# Heaters.net
KiCad netlist of a schematic drawn in Altium Designer
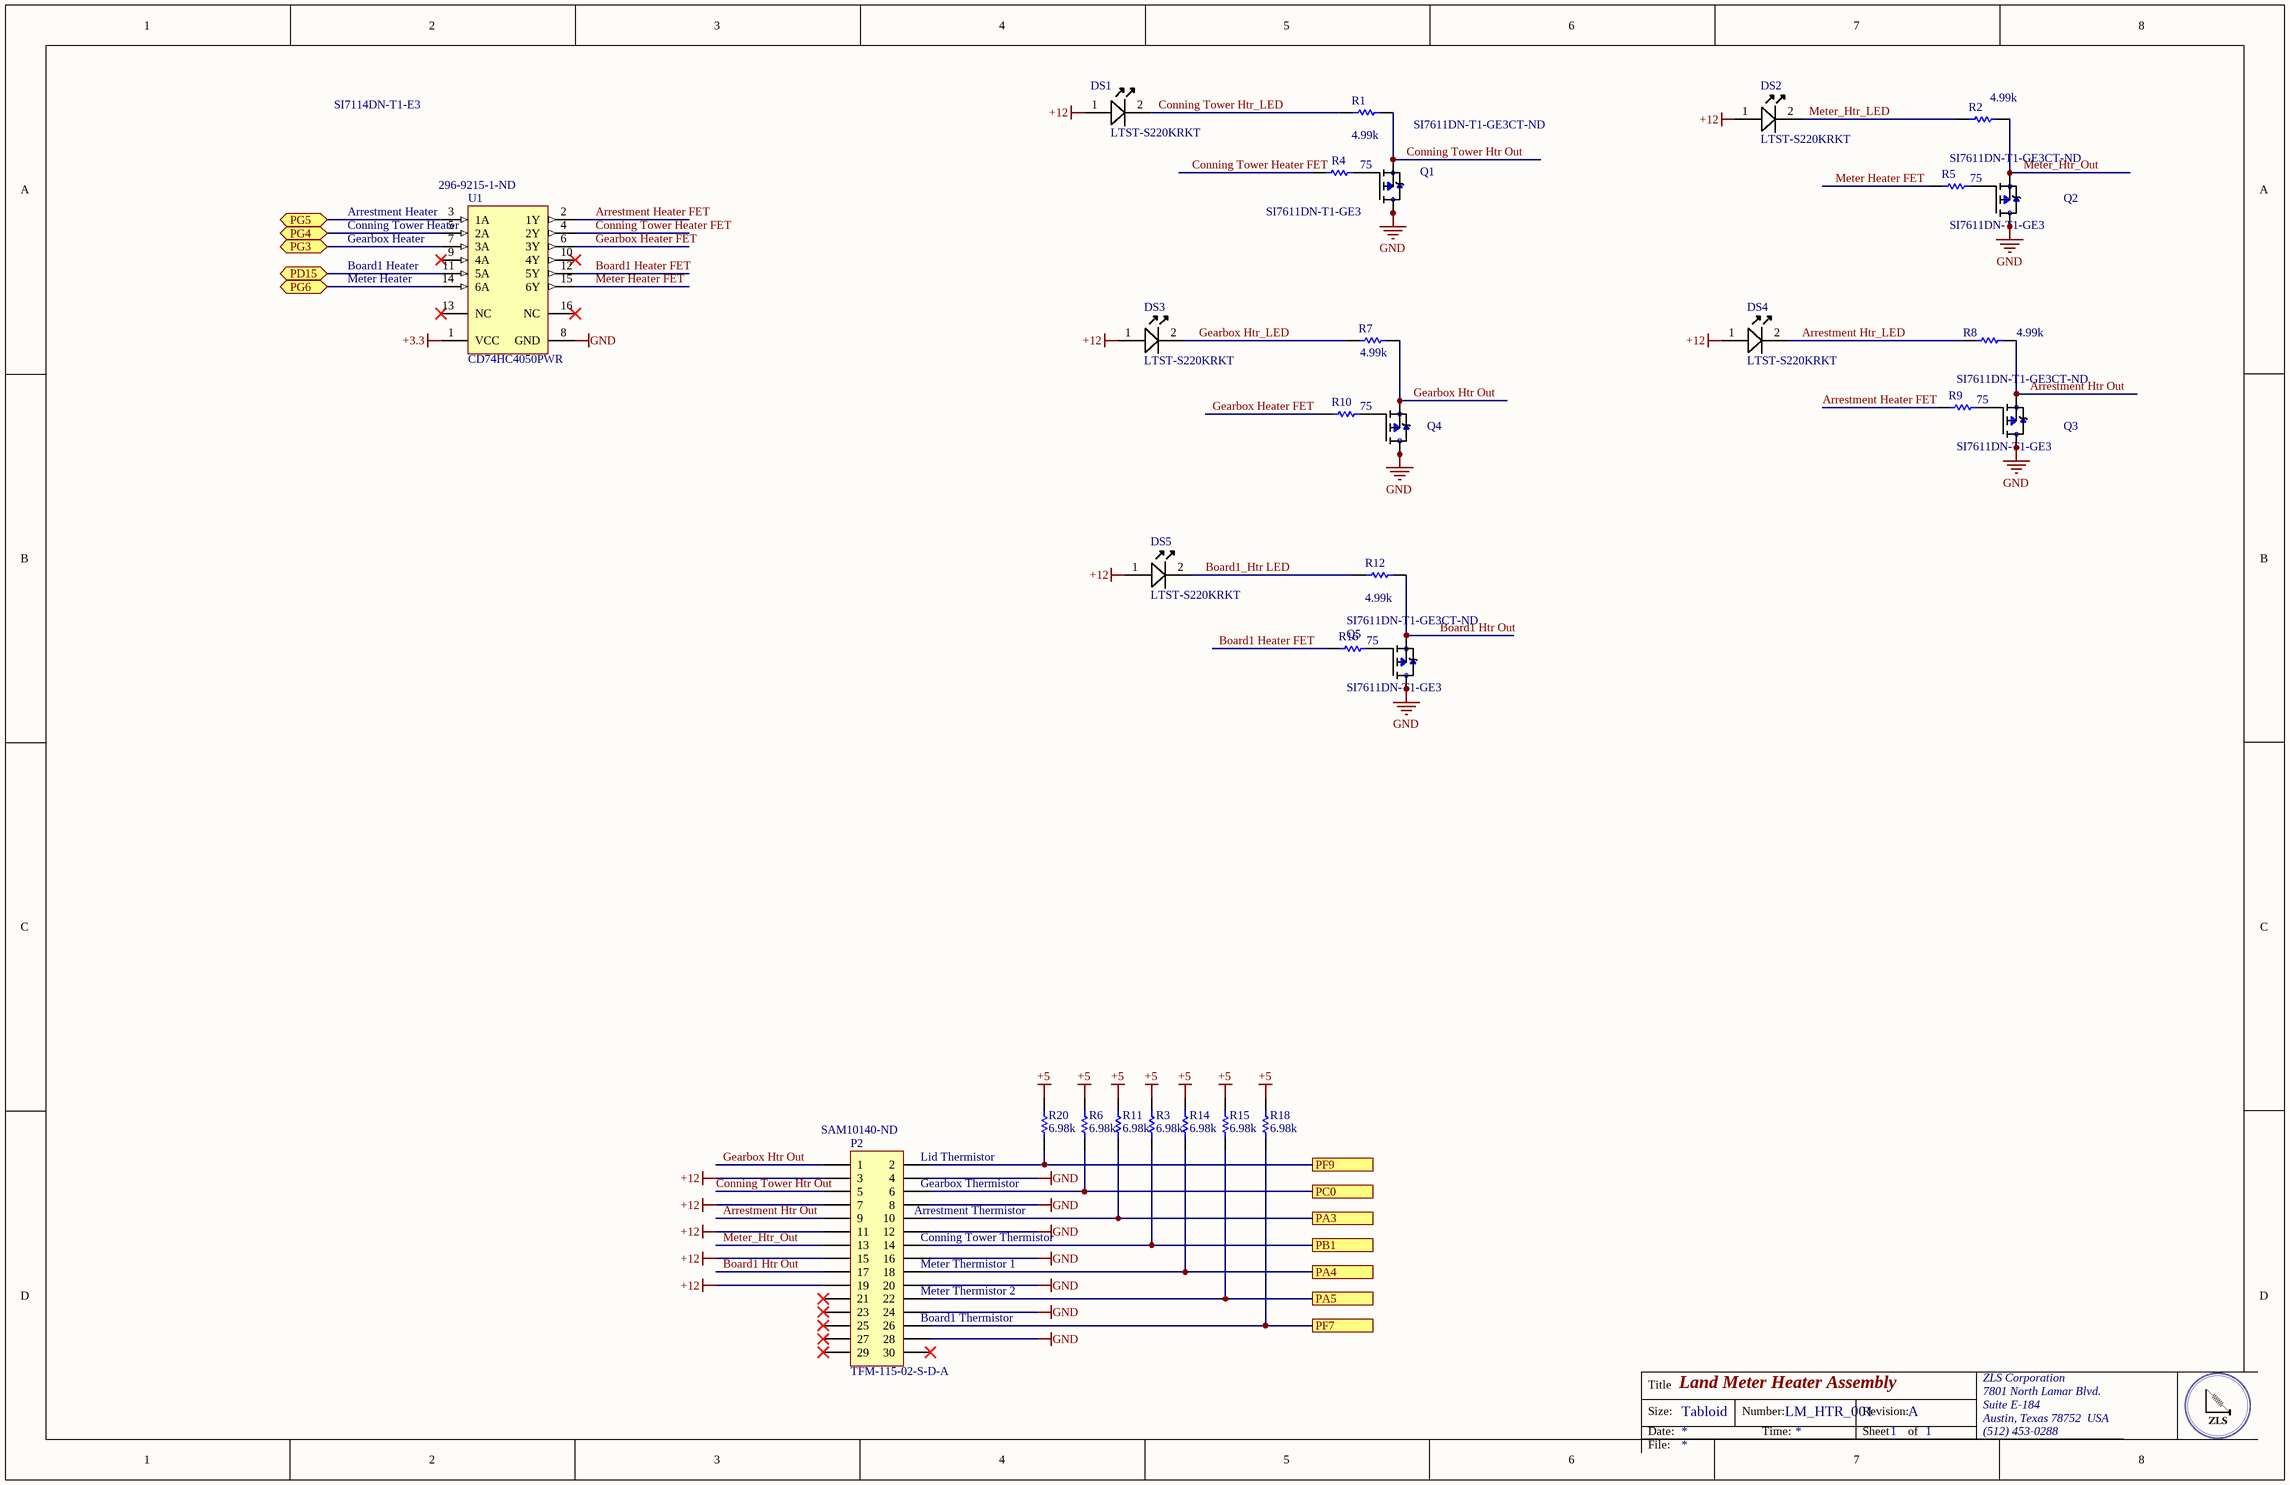
[diagram p0: Heaters.SchDoc]

(export (version "E")
  (design (tool "Eeschema 10.0.6"))
  (components
    (comp (ref "DS1")
      (value "Visible Name Value Type    False Description Lite-On LTST-S220KRKT Red LED, 631 nm 2012 (0805) Side View, Rectangle Lens SMD package STRING")
      (footprint "0805C_L")
      (fields
        (field (name "MANUFACTURER") "Vishay / Lite-On")
        (field (name "MANUFACTURER PART NUMBER") "LTST-S220KRKT")
      )
      (libsource (lib "*") (part "LED A/K"))
    )
    (comp (ref "DS2")
      (value "Visible Name Value Type    False Description Lite-On LTST-S220KRKT Red LED, 631 nm 2012 (0805) Side View, Rectangle Lens SMD package STRING")
      (footprint "0805C_L")
      (fields
        (field (name "MANUFACTURER") "Vishay / Lite-On")
        (field (name "MANUFACTURER PART NUMBER") "LTST-S220KRKT")
      )
      (libsource (lib "*") (part "LED A/K"))
    )
    (comp (ref "DS3")
      (value "Visible Name Value Type    False Description Lite-On LTST-S220KRKT Red LED, 631 nm 2012 (0805) Side View, Rectangle Lens SMD package STRING")
      (footprint "0805C_L")
      (fields
        (field (name "MANUFACTURER") "Vishay / Lite-On")
        (field (name "MANUFACTURER PART NUMBER") "LTST-S220KRKT")
      )
      (libsource (lib "*") (part "LED A/K"))
    )
    (comp (ref "DS4")
      (value "Visible Name Value Type    False Description Lite-On LTST-S220KRKT Red LED, 631 nm 2012 (0805) Side View, Rectangle Lens SMD package STRING")
      (footprint "0805C_L")
      (fields
        (field (name "MANUFACTURER") "Vishay / Lite-On")
        (field (name "MANUFACTURER PART NUMBER") "LTST-S220KRKT")
      )
      (libsource (lib "*") (part "LED A/K"))
    )
    (comp (ref "DS5")
      (value "Visible Name Value Type    False Description Lite-On LTST-S220KRKT Red LED, 631 nm 2012 (0805) Side View, Rectangle Lens SMD package STRING")
      (footprint "0805C_L")
      (fields
        (field (name "MANUFACTURER") "Vishay / Lite-On")
        (field (name "MANUFACTURER PART NUMBER") "LTST-S220KRKT")
      )
      (libsource (lib "*") (part "LED A/K"))
    )
    (comp (ref "P2")
      (value "TFM-115-02-S-D-A")
      (footprint "TFM-115-02-S-D-A - duplicate")
      (description "Header, 15-Pin, Dual row, Right Angle")
      (fields
        (field (name "SUPPLIER PART NUMBER 1") "SAM10140-ND")
        (field (name "MANUFACTURER") "Samtec")
        (field (name "PUBLISHER") "Altium Limited")
      )
      (libsource (lib "Miscellaneous Connectors") (part "Header 15X2H"))
    )
    (comp (ref "Q1")
      (value "SI7611DN-T1-GE3")
      (footprint "*VISHAY_SIS468DN-T1-GE3")
      (description "P-Channel 40 V 0.025 Ohm 39 W Surface Mount Power Mosfet - PowerPAK-1212-8")
      (fields
        (field (name "DIGI-KEY_PART_NUMBER") "SI7611DN-T1-GE3CT-ND")
        (field (name "MF") "Vishay Siliconix")
        (field (name "SUPPLIER PART NUMBER 1") "SI7611DN-T1-GE3CT-ND")
      )
      (libsource (lib "SI7611DN-T1-GE3") (part "SI7611DN-T1-GE3"))
    )
    (comp (ref "Q2")
      (value "SI7611DN-T1-GE3")
      (footprint "*VISHAY_SIS468DN-T1-GE3")
      (description "P-Channel 40 V 0.025 Ohm 39 W Surface Mount Power Mosfet - PowerPAK-1212-8")
      (fields
        (field (name "DIGI-KEY_PART_NUMBER") "SI7611DN-T1-GE3CT-ND")
        (field (name "MF") "Vishay Siliconix")
        (field (name "SUPPLIER PART NUMBER 1") "SI7611DN-T1-GE3CT-ND")
      )
      (libsource (lib "SI7611DN-T1-GE3") (part "SI7611DN-T1-GE3"))
    )
    (comp (ref "Q3")
      (value "SI7611DN-T1-GE3")
      (footprint "*VISHAY_SIS468DN-T1-GE3")
      (description "P-Channel 40 V 0.025 Ohm 39 W Surface Mount Power Mosfet - PowerPAK-1212-8")
      (fields
        (field (name "DIGI-KEY_PART_NUMBER") "SI7611DN-T1-GE3CT-ND")
        (field (name "MF") "Vishay Siliconix")
        (field (name "SUPPLIER PART NUMBER 1") "SI7611DN-T1-GE3CT-ND")
      )
      (libsource (lib "SI7611DN-T1-GE3") (part "SI7611DN-T1-GE3"))
    )
    (comp (ref "Q4")
      (value "SI7611DN-T1-GE3")
      (footprint "*VISHAY_SIS468DN-T1-GE3")
      (description "P-Channel 40 V 0.025 Ohm 39 W Surface Mount Power Mosfet - PowerPAK-1212-8")
      (fields
        (field (name "DIGI-KEY_PART_NUMBER") "SI7611DN-T1-GE3CT-ND")
        (field (name "MF") "Vishay Siliconix")
      )
      (libsource (lib "SI7611DN-T1-GE3") (part "SI7611DN-T1-GE3"))
    )
    (comp (ref "Q5")
      (value "SI7611DN-T1-GE3")
      (footprint "*VISHAY_SIS468DN-T1-GE3")
      (description "P-Channel 40 V 0.025 Ohm 39 W Surface Mount Power Mosfet - PowerPAK-1212-8")
      (fields
        (field (name "DIGI-KEY_PART_NUMBER") "SI7611DN-T1-GE3CT-ND")
        (field (name "MF") "Vishay Siliconix")
        (field (name "SUPPLIER PART NUMBER 1") "SI7611DN-T1-GE3CT-ND")
      )
      (libsource (lib "SI7611DN-T1-GE3") (part "SI7611DN-T1-GE3"))
    )
    (comp (ref "R1")
      (value "~")
      (footprint "RESC0805(2012)_L")
      (fields
        (field (name "MANUFACTURER") "Vishay Dale")
        (field (name "MANUFACTURER PART NUMBER") "CRCW08054K99FKEA")
        (field (name "RESISTANCE (OHMS)") "4.99k")
        (field (name "TOLERANCE") "±1%")
      )
      (libsource (lib "Altium Content Vault") (part "CMP-1013-00393-1"))
    )
    (comp (ref "R2")
      (value "~")
      (footprint "RESC0805(2012)_L")
      (fields
        (field (name "MANUFACTURER") "Vishay Dale")
        (field (name "MANUFACTURER PART NUMBER") "CRCW08054K99FKEA")
        (field (name "RESISTANCE (OHMS)") "4.99k")
        (field (name "TOLERANCE") "±1%")
      )
      (libsource (lib "Altium Content Vault") (part "CMP-1013-00393-1"))
    )
    (comp (ref "R3")
      (value "6K98 1% 0805(2012)")
      (footprint "RESC0805(2012)_N")
      (description "6K98 0.125W 1% 0805 (2012 Metric)  SMD")
      (fields
        (field (name "MANUFACTURER") "Vishay Dale")
        (field (name "MANUFACTURER PART NUMBER") "CRCW08056K98FKEA")
        (field (name "RESISTANCE (OHMS)") "6.98k")
      )
      (libsource (lib "Altium Content Vault") (part "CMP-1013-00606-1"))
    )
    (comp (ref "R4")
      (value "~")
      (footprint "RESC0805(2012)_L")
      (fields
        (field (name "MANUFACTURER") "Vishay Dale")
        (field (name "MANUFACTURER PART NUMBER") "CRCW080575R0FKEA")
        (field (name "RESISTANCE (OHMS)") "75")
        (field (name "TOLERANCE") "±1%")
      )
      (libsource (lib "Altium Content Vault") (part "CMP-1013-00393-1"))
    )
    (comp (ref "R5")
      (value "~")
      (footprint "RESC0805(2012)_L")
      (fields
        (field (name "MANUFACTURER") "Vishay Dale")
        (field (name "MANUFACTURER PART NUMBER") "CRCW080575R0FKEA")
        (field (name "RESISTANCE (OHMS)") "75")
        (field (name "TOLERANCE") "±1%")
      )
      (libsource (lib "Altium Content Vault") (part "CMP-1013-00393-1"))
    )
    (comp (ref "R6")
      (value "6K98 1% 0805(2012)")
      (footprint "RESC0805(2012)_N")
      (description "6K98 0.125W 1% 0805 (2012 Metric)  SMD")
      (fields
        (field (name "MANUFACTURER") "Vishay Dale")
        (field (name "MANUFACTURER PART NUMBER") "CRCW08056K98FKEA")
        (field (name "RESISTANCE (OHMS)") "6.98k")
      )
      (libsource (lib "Altium Content Vault") (part "CMP-1013-00606-1"))
    )
    (comp (ref "R7")
      (value "~")
      (footprint "RESC0805(2012)_L")
      (fields
        (field (name "MANUFACTURER") "Vishay Dale")
        (field (name "MANUFACTURER PART NUMBER") "CRCW08054K99FKEA")
        (field (name "RESISTANCE (OHMS)") "4.99k")
        (field (name "TOLERANCE") "±1%")
      )
      (libsource (lib "Altium Content Vault") (part "CMP-1013-00393-1"))
    )
    (comp (ref "R8")
      (value "~")
      (footprint "RESC0805(2012)_L")
      (fields
        (field (name "MANUFACTURER") "Vishay Dale")
        (field (name "MANUFACTURER PART NUMBER") "CRCW08054K99FKEA")
        (field (name "RESISTANCE (OHMS)") "4.99k")
        (field (name "TOLERANCE") "±1%")
      )
      (libsource (lib "Altium Content Vault") (part "CMP-1013-00393-1"))
    )
    (comp (ref "R9")
      (value "~")
      (footprint "RESC0805(2012)_L")
      (fields
        (field (name "MANUFACTURER") "Vishay Dale")
        (field (name "MANUFACTURER PART NUMBER") "CRCW080575R0FKEA")
        (field (name "RESISTANCE (OHMS)") "75")
        (field (name "TOLERANCE") "±1%")
      )
      (libsource (lib "Altium Content Vault") (part "CMP-1013-00393-1"))
    )
    (comp (ref "R10")
      (value "~")
      (footprint "RESC0805(2012)_L")
      (fields
        (field (name "MANUFACTURER") "Vishay Dale")
        (field (name "MANUFACTURER PART NUMBER") "CRCW080575R0FKEA")
        (field (name "RESISTANCE (OHMS)") "75")
        (field (name "TOLERANCE") "±1%")
      )
      (libsource (lib "Altium Content Vault") (part "CMP-1013-00393-1"))
    )
    (comp (ref "R11")
      (value "6K98 1% 0805(2012)")
      (footprint "RESC0805(2012)_N")
      (description "6K98 0.125W 1% 0805 (2012 Metric)  SMD")
      (fields
        (field (name "MANUFACTURER") "Vishay Dale")
        (field (name "MANUFACTURER PART NUMBER") "CRCW08056K98FKEA")
        (field (name "RESISTANCE (OHMS)") "6.98k")
      )
      (libsource (lib "Altium Content Vault") (part "CMP-1013-00606-1"))
    )
    (comp (ref "R12")
      (value "~")
      (footprint "RESC0805(2012)_L")
      (fields
        (field (name "MANUFACTURER") "Vishay Dale")
        (field (name "MANUFACTURER PART NUMBER") "CRCW08054K99FKEA")
        (field (name "RESISTANCE (OHMS)") "4.99k")
        (field (name "TOLERANCE") "±1%")
      )
      (libsource (lib "Altium Content Vault") (part "CMP-1013-00393-1"))
    )
    (comp (ref "R14")
      (value "6K98 1% 0805(2012)")
      (footprint "RESC0805(2012)_N")
      (description "6K98 0.125W 1% 0805 (2012 Metric)  SMD")
      (fields
        (field (name "MANUFACTURER") "Vishay Dale")
        (field (name "MANUFACTURER PART NUMBER") "CRCW08056K98FKEA")
        (field (name "RESISTANCE (OHMS)") "6.98k")
      )
      (libsource (lib "Altium Content Vault") (part "CMP-1013-00606-1"))
    )
    (comp (ref "R15")
      (value "6K98 1% 0805(2012)")
      (footprint "RESC0805(2012)_N")
      (description "6K98 0.125W 1% 0805 (2012 Metric)  SMD")
      (fields
        (field (name "MANUFACTURER") "Vishay Dale")
        (field (name "MANUFACTURER PART NUMBER") "CRCW08056K98FKEA")
        (field (name "RESISTANCE (OHMS)") "6.98k")
      )
      (libsource (lib "Altium Content Vault") (part "CMP-1013-00606-1"))
    )
    (comp (ref "R16")
      (value "~")
      (footprint "RESC0805(2012)_L")
      (fields
        (field (name "MANUFACTURER") "Vishay Dale")
        (field (name "MANUFACTURER PART NUMBER") "CRCW080575R0FKEA")
        (field (name "RESISTANCE (OHMS)") "75")
        (field (name "TOLERANCE") "±1%")
      )
      (libsource (lib "Altium Content Vault") (part "CMP-1013-00393-1"))
    )
    (comp (ref "R18")
      (value "6K98 1% 0805(2012)")
      (footprint "RESC0805(2012)_N")
      (description "6K98 0.125W 1% 0805 (2012 Metric)  SMD")
      (fields
        (field (name "MANUFACTURER") "Vishay Dale")
        (field (name "MANUFACTURER PART NUMBER") "CRCW08056K98FKEA")
        (field (name "RESISTANCE (OHMS)") "6.98k")
      )
      (libsource (lib "Altium Content Vault") (part "CMP-1013-00606-1"))
    )
    (comp (ref "R20")
      (value "6K98 1% 0805(2012)")
      (footprint "RESC0805(2012)_N")
      (description "6K98 0.125W 1% 0805 (2012 Metric)  SMD")
      (fields
        (field (name "MANUFACTURER") "Vishay Dale")
        (field (name "MANUFACTURER PART NUMBER") "CRCW08056K98FKEA")
        (field (name "RESISTANCE (OHMS)") "6.98k")
      )
      (libsource (lib "Altium Content Vault") (part "CMP-1013-00606-1"))
    )
    (comp (ref "U1")
      (value "CD74HC4050PWR")
      (footprint "PW0016A_N")
      (description "High Speed CMOS Logic Hex Non-Inverting Buffers, PW0016A, LARGE T&R")
      (fields
        (field (name "GENERIC PART NUMBER") "CD74HC4050")
        (field (name "MANUFACTURER") "Texas Instruments")
        (field (name "SUPPLIER PART NUMBER 1") "296-9215-1-ND")
      )
      (libsource (lib "Altium Content Vault") (part "TI-CDX4HC4050-16"))
    )
  )
  (nets
    (net (code "1") (name "+3.3") (class "Default")
      (node (ref "U1") (pin "1") (pinfunction "VCC_1") (pintype "power_in"))
    )
    (net (code "2") (name "+5") (class "Default")
      (node (ref "R11") (pin "1") (pinfunction "1_1") (pintype "passive"))
      (node (ref "R14") (pin "1") (pinfunction "1_1") (pintype "passive"))
      (node (ref "R15") (pin "2") (pinfunction "2_2") (pintype "passive"))
      (node (ref "R18") (pin "1") (pinfunction "1_1") (pintype "passive"))
      (node (ref "R20") (pin "1") (pinfunction "1_1") (pintype "passive"))
      (node (ref "R3") (pin "2") (pinfunction "2_2") (pintype "passive"))
      (node (ref "R6") (pin "2") (pinfunction "2_2") (pintype "passive"))
    )
    (net (code "3") (name "+12") (class "Default")
      (node (ref "DS1") (pin "1") (pinfunction "A_1") (pintype "passive"))
      (node (ref "DS2") (pin "1") (pinfunction "A_1") (pintype "passive"))
      (node (ref "DS3") (pin "1") (pinfunction "A_1") (pintype "passive"))
      (node (ref "DS4") (pin "1") (pinfunction "A_1") (pintype "passive"))
      (node (ref "DS5") (pin "1") (pinfunction "A_1") (pintype "passive"))
      (node (ref "P2") (pin "11") (pinfunction "11_11") (pintype "passive"))
      (node (ref "P2") (pin "15") (pinfunction "15_15") (pintype "passive"))
      (node (ref "P2") (pin "19") (pinfunction "19_19") (pintype "passive"))
      (node (ref "P2") (pin "3") (pinfunction "3_3") (pintype "passive"))
      (node (ref "P2") (pin "7") (pinfunction "7_7") (pintype "passive"))
    )
    (net (code "4") (name "/Arrestment Heater FET") (class "Default")
      (node (ref "R9") (pin "1") (pinfunction "1_1") (pintype "passive"))
      (node (ref "U1") (pin "2") (pinfunction "1Y_2") (pintype "output"))
    )
    (net (code "5") (name "/Arrestment Htr Out") (class "Default")
      (node (ref "P2") (pin "9") (pinfunction "9_9") (pintype "passive"))
      (node (ref "Q3") (pin "1") (pinfunction "S_1") (pintype "passive"))
      (node (ref "Q3") (pin "2") (pinfunction "S_2") (pintype "passive"))
      (node (ref "Q3") (pin "3") (pinfunction "S_3") (pintype "passive"))
      (node (ref "R8") (pin "2") (pinfunction "2_2") (pintype "passive"))
    )
    (net (code "6") (name "/Arrestment Htr_LED") (class "Default")
      (node (ref "DS4") (pin "2") (pinfunction "K_2") (pintype "passive"))
      (node (ref "R8") (pin "1") (pinfunction "1_1") (pintype "passive"))
    )
    (net (code "7") (name "/Board1 Heater FET") (class "Default")
      (node (ref "R16") (pin "1") (pinfunction "1_1") (pintype "passive"))
      (node (ref "U1") (pin "12") (pinfunction "5Y_12") (pintype "output"))
    )
    (net (code "8") (name "/Board1 Htr Out") (class "Default")
      (node (ref "P2") (pin "17") (pinfunction "17_17") (pintype "passive"))
      (node (ref "Q5") (pin "1") (pinfunction "S_1") (pintype "passive"))
      (node (ref "Q5") (pin "2") (pinfunction "S_2") (pintype "passive"))
      (node (ref "Q5") (pin "3") (pinfunction "S_3") (pintype "passive"))
      (node (ref "R12") (pin "1") (pinfunction "1_1") (pintype "passive"))
    )
    (net (code "9") (name "/Board1_Htr LED") (class "Default")
      (node (ref "DS5") (pin "2") (pinfunction "K_2") (pintype "passive"))
      (node (ref "R12") (pin "2") (pinfunction "2_2") (pintype "passive"))
    )
    (net (code "10") (name "/Conning Tower Heater FET") (class "Default")
      (node (ref "R4") (pin "1") (pinfunction "1_1") (pintype "passive"))
      (node (ref "U1") (pin "4") (pinfunction "2Y_4") (pintype "output"))
    )
    (net (code "11") (name "/Conning Tower Htr Out") (class "Default")
      (node (ref "P2") (pin "5") (pinfunction "5_5") (pintype "passive"))
      (node (ref "Q1") (pin "1") (pinfunction "S_1") (pintype "passive"))
      (node (ref "Q1") (pin "2") (pinfunction "S_2") (pintype "passive"))
      (node (ref "Q1") (pin "3") (pinfunction "S_3") (pintype "passive"))
      (node (ref "R1") (pin "1") (pinfunction "1_1") (pintype "passive"))
    )
    (net (code "12") (name "/Conning Tower Htr_LED") (class "Default")
      (node (ref "DS1") (pin "2") (pinfunction "K_2") (pintype "passive"))
      (node (ref "R1") (pin "2") (pinfunction "2_2") (pintype "passive"))
    )
    (net (code "13") (name "/Gearbox Heater FET") (class "Default")
      (node (ref "R10") (pin "1") (pinfunction "1_1") (pintype "passive"))
      (node (ref "U1") (pin "6") (pinfunction "3Y_6") (pintype "output"))
    )
    (net (code "14") (name "/Gearbox Htr Out") (class "Default")
      (node (ref "P2") (pin "1") (pinfunction "1_1") (pintype "passive"))
      (node (ref "Q4") (pin "1") (pinfunction "S_1") (pintype "passive"))
      (node (ref "Q4") (pin "2") (pinfunction "S_2") (pintype "passive"))
      (node (ref "Q4") (pin "3") (pinfunction "S_3") (pintype "passive"))
      (node (ref "R7") (pin "1") (pinfunction "1_1") (pintype "passive"))
    )
    (net (code "15") (name "/Gearbox Htr_LED") (class "Default")
      (node (ref "DS3") (pin "2") (pinfunction "K_2") (pintype "passive"))
      (node (ref "R7") (pin "2") (pinfunction "2_2") (pintype "passive"))
    )
    (net (code "16") (name "/Meter Heater FET") (class "Default")
      (node (ref "R5") (pin "1") (pinfunction "1_1") (pintype "passive"))
      (node (ref "U1") (pin "15") (pinfunction "6Y_15") (pintype "output"))
    )
    (net (code "17") (name "/Meter_Htr_LED") (class "Default")
      (node (ref "DS2") (pin "2") (pinfunction "K_2") (pintype "passive"))
      (node (ref "R2") (pin "1") (pinfunction "1_1") (pintype "passive"))
    )
    (net (code "18") (name "/Meter_Htr_Out") (class "Default")
      (node (ref "P2") (pin "13") (pinfunction "13_13") (pintype "passive"))
      (node (ref "Q2") (pin "1") (pinfunction "S_1") (pintype "passive"))
      (node (ref "Q2") (pin "2") (pinfunction "S_2") (pintype "passive"))
      (node (ref "Q2") (pin "3") (pinfunction "S_3") (pintype "passive"))
      (node (ref "R2") (pin "2") (pinfunction "2_2") (pintype "passive"))
    )
    (net (code "19") (name "/PA3") (class "Default")
      (node (ref "P2") (pin "10") (pinfunction "10_10") (pintype "passive"))
      (node (ref "R11") (pin "2") (pinfunction "2_2") (pintype "passive"))
    )
    (net (code "20") (name "/PA4") (class "Default")
      (node (ref "P2") (pin "18") (pinfunction "18_18") (pintype "passive"))
      (node (ref "R14") (pin "2") (pinfunction "2_2") (pintype "passive"))
    )
    (net (code "21") (name "/PA5") (class "Default")
      (node (ref "P2") (pin "22") (pinfunction "22_22") (pintype "passive"))
      (node (ref "R15") (pin "1") (pinfunction "1_1") (pintype "passive"))
    )
    (net (code "22") (name "/PB1") (class "Default")
      (node (ref "P2") (pin "14") (pinfunction "14_14") (pintype "passive"))
      (node (ref "R3") (pin "1") (pinfunction "1_1") (pintype "passive"))
    )
    (net (code "23") (name "/PC0") (class "Default")
      (node (ref "P2") (pin "6") (pinfunction "6_6") (pintype "passive"))
      (node (ref "R6") (pin "1") (pinfunction "1_1") (pintype "passive"))
    )
    (net (code "24") (name "/PD15") (class "Default")
      (node (ref "U1") (pin "11") (pinfunction "5A_11") (pintype "input"))
    )
    (net (code "25") (name "/PF7") (class "Default")
      (node (ref "P2") (pin "26") (pinfunction "26_26") (pintype "passive"))
      (node (ref "R18") (pin "2") (pinfunction "2_2") (pintype "passive"))
    )
    (net (code "26") (name "/PF9") (class "Default")
      (node (ref "P2") (pin "2") (pinfunction "2_2") (pintype "passive"))
      (node (ref "R20") (pin "2") (pinfunction "2_2") (pintype "passive"))
    )
    (net (code "27") (name "/PG3") (class "Default")
      (node (ref "U1") (pin "7") (pinfunction "3A_7") (pintype "input"))
    )
    (net (code "28") (name "/PG4") (class "Default")
      (node (ref "U1") (pin "5") (pinfunction "2A_5") (pintype "input"))
    )
    (net (code "29") (name "/PG5") (class "Default")
      (node (ref "U1") (pin "3") (pinfunction "1A_3") (pintype "input"))
    )
    (net (code "30") (name "/PG6") (class "Default")
      (node (ref "U1") (pin "14") (pinfunction "6A_14") (pintype "input"))
    )
    (net (code "31") (name "GND") (class "Default")
      (node (ref "P2") (pin "12") (pinfunction "12_12") (pintype "passive"))
      (node (ref "P2") (pin "16") (pinfunction "16_16") (pintype "passive"))
      (node (ref "P2") (pin "20") (pinfunction "20_20") (pintype "passive"))
      (node (ref "P2") (pin "24") (pinfunction "24_24") (pintype "passive"))
      (node (ref "P2") (pin "28") (pinfunction "28_28") (pintype "passive"))
      (node (ref "P2") (pin "4") (pinfunction "4_4") (pintype "passive"))
      (node (ref "P2") (pin "8") (pinfunction "8_8") (pintype "passive"))
      (node (ref "Q1") (pin "5") (pinfunction "D_5") (pintype "passive"))
      (node (ref "Q1") (pin "6") (pinfunction "D_6") (pintype "passive"))
      (node (ref "Q1") (pin "7") (pinfunction "D_7") (pintype "passive"))
      (node (ref "Q1") (pin "8") (pinfunction "D_8") (pintype "passive"))
      (node (ref "Q1") (pin "9") (pinfunction "D_9") (pintype "passive"))
      (node (ref "Q2") (pin "5") (pinfunction "D_5") (pintype "passive"))
      (node (ref "Q2") (pin "6") (pinfunction "D_6") (pintype "passive"))
      (node (ref "Q2") (pin "7") (pinfunction "D_7") (pintype "passive"))
      (node (ref "Q2") (pin "8") (pinfunction "D_8") (pintype "passive"))
      (node (ref "Q2") (pin "9") (pinfunction "D_9") (pintype "passive"))
      (node (ref "Q3") (pin "5") (pinfunction "D_5") (pintype "passive"))
      (node (ref "Q3") (pin "6") (pinfunction "D_6") (pintype "passive"))
      (node (ref "Q3") (pin "7") (pinfunction "D_7") (pintype "passive"))
      (node (ref "Q3") (pin "8") (pinfunction "D_8") (pintype "passive"))
      (node (ref "Q3") (pin "9") (pinfunction "D_9") (pintype "passive"))
      (node (ref "Q4") (pin "5") (pinfunction "D_5") (pintype "passive"))
      (node (ref "Q4") (pin "6") (pinfunction "D_6") (pintype "passive"))
      (node (ref "Q4") (pin "7") (pinfunction "D_7") (pintype "passive"))
      (node (ref "Q4") (pin "8") (pinfunction "D_8") (pintype "passive"))
      (node (ref "Q4") (pin "9") (pinfunction "D_9") (pintype "passive"))
      (node (ref "Q5") (pin "5") (pinfunction "D_5") (pintype "passive"))
      (node (ref "Q5") (pin "6") (pinfunction "D_6") (pintype "passive"))
      (node (ref "Q5") (pin "7") (pinfunction "D_7") (pintype "passive"))
      (node (ref "Q5") (pin "8") (pinfunction "D_8") (pintype "passive"))
      (node (ref "Q5") (pin "9") (pinfunction "D_9") (pintype "passive"))
      (node (ref "U1") (pin "8") (pinfunction "GND_8") (pintype "power_in"))
    )
    (net (code "32") (name "Net-(Q1-G)") (class "Default")
      (node (ref "Q1") (pin "4") (pinfunction "G_4") (pintype "passive"))
      (node (ref "R4") (pin "2") (pinfunction "2_2") (pintype "passive"))
    )
    (net (code "33") (name "Net-(Q2-G)") (class "Default")
      (node (ref "Q2") (pin "4") (pinfunction "G_4") (pintype "passive"))
      (node (ref "R5") (pin "2") (pinfunction "2_2") (pintype "passive"))
    )
    (net (code "34") (name "Net-(Q3-G)") (class "Default")
      (node (ref "Q3") (pin "4") (pinfunction "G_4") (pintype "passive"))
      (node (ref "R9") (pin "2") (pinfunction "2_2") (pintype "passive"))
    )
    (net (code "35") (name "Net-(Q4-G)") (class "Default")
      (node (ref "Q4") (pin "4") (pinfunction "G_4") (pintype "passive"))
      (node (ref "R10") (pin "2") (pinfunction "2_2") (pintype "passive"))
    )
    (net (code "36") (name "Net-(Q5-G)") (class "Default")
      (node (ref "Q5") (pin "4") (pinfunction "G_4") (pintype "passive"))
      (node (ref "R16") (pin "2") (pinfunction "2_2") (pintype "passive"))
    )
    (net (code "37") (name "unconnected-(P2-Pad21)") (class "Default")
      (node (ref "P2") (pin "21") (pinfunction "21_21") (pintype "passive+no_connect"))
    )
    (net (code "38") (name "unconnected-(P2-Pad23)") (class "Default")
      (node (ref "P2") (pin "23") (pinfunction "23_23") (pintype "passive+no_connect"))
    )
    (net (code "39") (name "unconnected-(P2-Pad25)") (class "Default")
      (node (ref "P2") (pin "25") (pinfunction "25_25") (pintype "passive+no_connect"))
    )
    (net (code "40") (name "unconnected-(P2-Pad27)") (class "Default")
      (node (ref "P2") (pin "27") (pinfunction "27_27") (pintype "passive+no_connect"))
    )
    (net (code "41") (name "unconnected-(P2-Pad29)") (class "Default")
      (node (ref "P2") (pin "29") (pinfunction "29_29") (pintype "passive+no_connect"))
    )
    (net (code "42") (name "unconnected-(P2-Pad30)") (class "Default")
      (node (ref "P2") (pin "30") (pinfunction "30_30") (pintype "passive+no_connect"))
    )
    (net (code "43") (name "unconnected-(U1-4A-Pad9)") (class "Default")
      (node (ref "U1") (pin "9") (pinfunction "4A_9") (pintype "input+no_connect"))
    )
    (net (code "44") (name "unconnected-(U1-4Y-Pad10)") (class "Default")
      (node (ref "U1") (pin "10") (pinfunction "4Y_10") (pintype "output+no_connect"))
    )
    (net (code "45") (name "unconnected-(U1-NC-Pad13)") (class "Default")
      (node (ref "U1") (pin "13") (pinfunction "NC_13") (pintype "passive+no_connect"))
    )
    (net (code "46") (name "unconnected-(U1-NC-Pad16)") (class "Default")
      (node (ref "U1") (pin "16") (pinfunction "NC_16") (pintype "passive+no_connect"))
    )
  )
)
